# Rev1.net
KiCad netlist of a schematic drawn in EAGLE
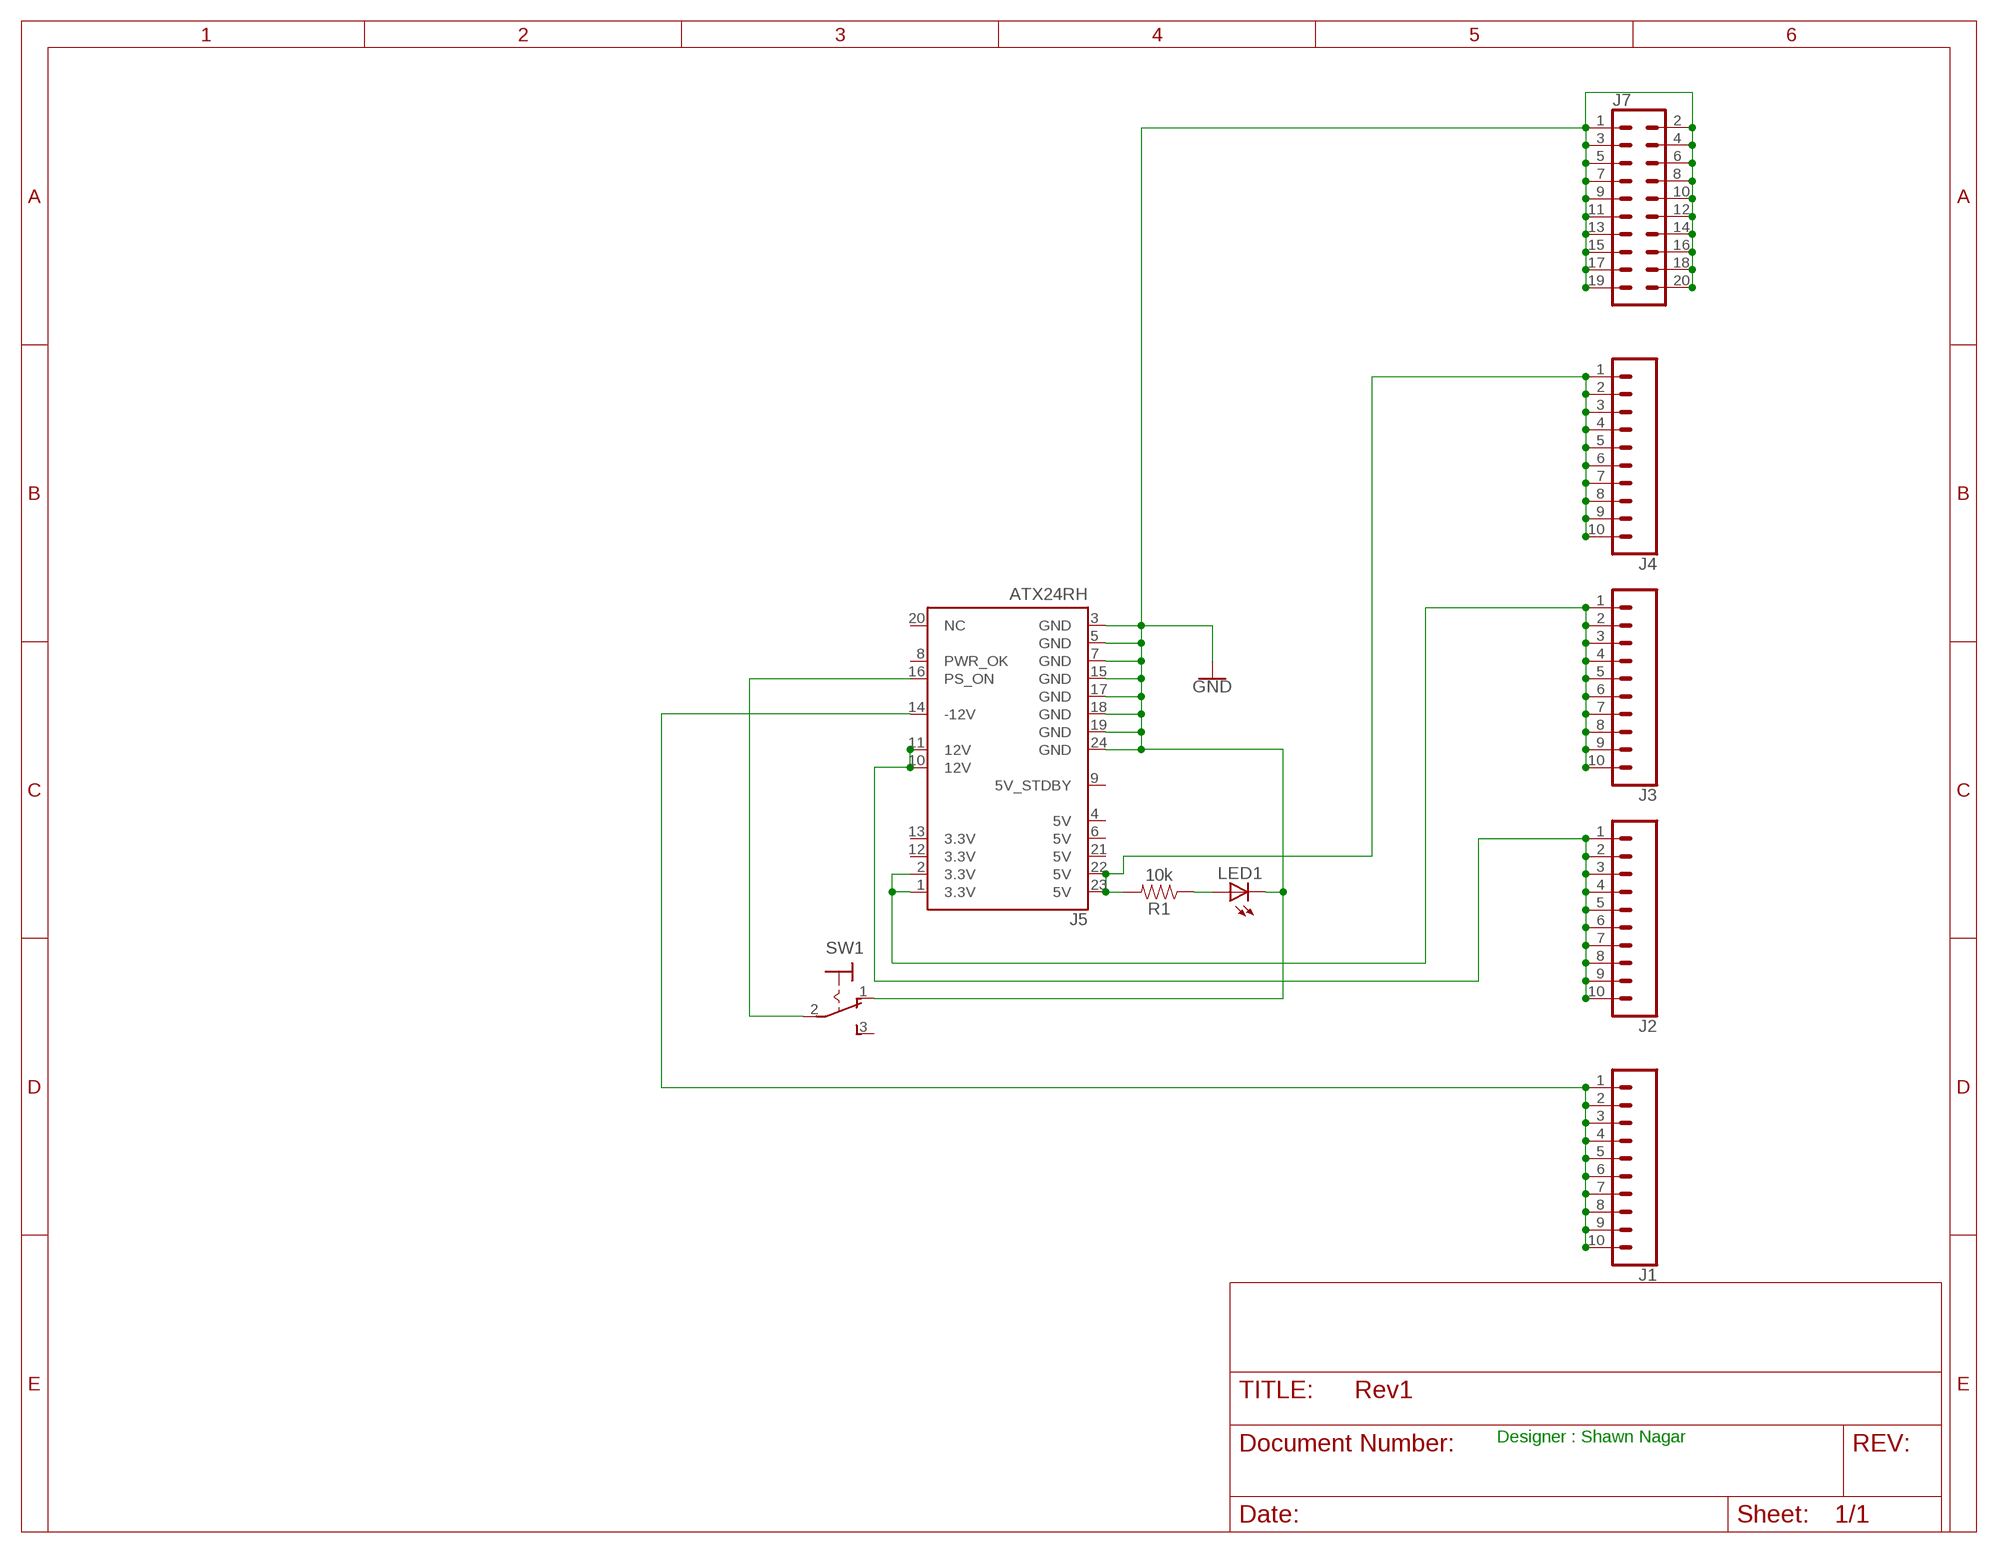
[diagram p0: schematic, sheet 1]

(export (version "E")
  (design (tool "Eeschema 10.0.6"))
  (components
    (comp (ref "J1")
      (value "CONN_10\"")
      (footprint "eagle-import:1X10")
      (libsource (lib "eagle-import") (part "CONN_10{dblquote}"))
    )
    (comp (ref "J2")
      (value "CONN_10\"")
      (footprint "eagle-import:1X10")
      (libsource (lib "eagle-import") (part "CONN_10{dblquote}"))
    )
    (comp (ref "J3")
      (value "CONN_10\"")
      (footprint "eagle-import:1X10")
      (libsource (lib "eagle-import") (part "CONN_10{dblquote}"))
    )
    (comp (ref "J4")
      (value "CONN_10\"")
      (footprint "eagle-import:1X10")
      (libsource (lib "eagle-import") (part "CONN_10{dblquote}"))
    )
    (comp (ref "J5")
      (value "ATX24RH")
      (footprint "eagle-import:ATX24_RIGHT_ANGLE")
      (libsource (lib "eagle-import") (part "ATX24RH"))
    )
    (comp (ref "J7")
      (value "CONN_10X2")
      (footprint "eagle-import:2X10")
      (libsource (lib "eagle-import") (part "CONN_10X2"))
    )
    (comp (ref "LED1")
      (value "LED5MM")
      (footprint "eagle-import:LED5MM")
      (libsource (lib "eagle-import") (part "LED5MM"))
    )
    (comp (ref "R1")
      (value "10k")
      (footprint "eagle-import:AXIAL-0.3")
      (libsource (lib "eagle-import") (part "10KOHM-HORIZ-1/4W-1%"))
    )
    (comp (ref "SW1")
      (value "320-916")
      (footprint "eagle-import:320-916")
      (libsource (lib "eagle-import") (part "320-916"))
    )
  )
  (nets
    (net (code "1") (name "GND") (class "Default")
      (node (ref "J5") (pin "15") (pinfunction "GND_15") (pintype "bidirectional"))
      (node (ref "J5") (pin "17") (pinfunction "GND_17") (pintype "bidirectional"))
      (node (ref "J5") (pin "18") (pinfunction "GND_18") (pintype "bidirectional"))
      (node (ref "J5") (pin "19") (pinfunction "GND_19") (pintype "bidirectional"))
      (node (ref "J5") (pin "24") (pinfunction "GND_24") (pintype "bidirectional"))
      (node (ref "J5") (pin "3") (pinfunction "GND_3") (pintype "bidirectional"))
      (node (ref "J5") (pin "5") (pinfunction "GND_5") (pintype "bidirectional"))
      (node (ref "J5") (pin "7") (pinfunction "GND_7") (pintype "bidirectional"))
      (node (ref "J7") (pin "1") (pinfunction "1_1") (pintype "passive"))
      (node (ref "J7") (pin "10") (pinfunction "10_10") (pintype "passive"))
      (node (ref "J7") (pin "11") (pinfunction "11_11") (pintype "passive"))
      (node (ref "J7") (pin "12") (pinfunction "12_12") (pintype "passive"))
      (node (ref "J7") (pin "13") (pinfunction "13_13") (pintype "passive"))
      (node (ref "J7") (pin "14") (pinfunction "14_14") (pintype "passive"))
      (node (ref "J7") (pin "15") (pinfunction "15_15") (pintype "passive"))
      (node (ref "J7") (pin "16") (pinfunction "16_16") (pintype "passive"))
      (node (ref "J7") (pin "17") (pinfunction "17_17") (pintype "passive"))
      (node (ref "J7") (pin "18") (pinfunction "18_18") (pintype "passive"))
      (node (ref "J7") (pin "19") (pinfunction "19_19") (pintype "passive"))
      (node (ref "J7") (pin "2") (pinfunction "2_2") (pintype "passive"))
      (node (ref "J7") (pin "20") (pinfunction "20_20") (pintype "passive"))
      (node (ref "J7") (pin "3") (pinfunction "3_3") (pintype "passive"))
      (node (ref "J7") (pin "4") (pinfunction "4_4") (pintype "passive"))
      (node (ref "J7") (pin "5") (pinfunction "5_5") (pintype "passive"))
      (node (ref "J7") (pin "6") (pinfunction "6_6") (pintype "passive"))
      (node (ref "J7") (pin "7") (pinfunction "7_7") (pintype "passive"))
      (node (ref "J7") (pin "8") (pinfunction "8_8") (pintype "passive"))
      (node (ref "J7") (pin "9") (pinfunction "9_9") (pintype "passive"))
      (node (ref "LED1") (pin "K") (pinfunction "C_K") (pintype "passive"))
      (node (ref "SW1") (pin "1") (pinfunction "O_1") (pintype "passive"))
    )
    (net (code "2") (name "Net-(J2-Pad1)") (class "Default")
      (node (ref "J2") (pin "1") (pinfunction "1_1") (pintype "passive"))
      (node (ref "J2") (pin "10") (pinfunction "10_10") (pintype "passive"))
      (node (ref "J2") (pin "2") (pinfunction "2_2") (pintype "passive"))
      (node (ref "J2") (pin "3") (pinfunction "3_3") (pintype "passive"))
      (node (ref "J2") (pin "4") (pinfunction "4_4") (pintype "passive"))
      (node (ref "J2") (pin "5") (pinfunction "5_5") (pintype "passive"))
      (node (ref "J2") (pin "6") (pinfunction "6_6") (pintype "passive"))
      (node (ref "J2") (pin "7") (pinfunction "7_7") (pintype "passive"))
      (node (ref "J2") (pin "8") (pinfunction "8_8") (pintype "passive"))
      (node (ref "J2") (pin "9") (pinfunction "9_9") (pintype "passive"))
      (node (ref "J5") (pin "10") (pinfunction "12V_10") (pintype "bidirectional"))
      (node (ref "J5") (pin "11") (pinfunction "12V_11") (pintype "bidirectional"))
    )
    (net (code "3") (name "Net-(J3-Pad1)") (class "Default")
      (node (ref "J3") (pin "1") (pinfunction "1_1") (pintype "passive"))
      (node (ref "J3") (pin "10") (pinfunction "10_10") (pintype "passive"))
      (node (ref "J3") (pin "2") (pinfunction "2_2") (pintype "passive"))
      (node (ref "J3") (pin "3") (pinfunction "3_3") (pintype "passive"))
      (node (ref "J3") (pin "4") (pinfunction "4_4") (pintype "passive"))
      (node (ref "J3") (pin "5") (pinfunction "5_5") (pintype "passive"))
      (node (ref "J3") (pin "6") (pinfunction "6_6") (pintype "passive"))
      (node (ref "J3") (pin "7") (pinfunction "7_7") (pintype "passive"))
      (node (ref "J3") (pin "8") (pinfunction "8_8") (pintype "passive"))
      (node (ref "J3") (pin "9") (pinfunction "9_9") (pintype "passive"))
      (node (ref "J5") (pin "1") (pinfunction "3.3V_1") (pintype "bidirectional"))
      (node (ref "J5") (pin "2") (pinfunction "3.3V_2") (pintype "bidirectional"))
    )
    (net (code "4") (name "Net-(J5--12V)") (class "Default")
      (node (ref "J1") (pin "1") (pinfunction "1_1") (pintype "passive"))
      (node (ref "J1") (pin "10") (pinfunction "10_10") (pintype "passive"))
      (node (ref "J1") (pin "2") (pinfunction "2_2") (pintype "passive"))
      (node (ref "J1") (pin "3") (pinfunction "3_3") (pintype "passive"))
      (node (ref "J1") (pin "4") (pinfunction "4_4") (pintype "passive"))
      (node (ref "J1") (pin "5") (pinfunction "5_5") (pintype "passive"))
      (node (ref "J1") (pin "6") (pinfunction "6_6") (pintype "passive"))
      (node (ref "J1") (pin "7") (pinfunction "7_7") (pintype "passive"))
      (node (ref "J1") (pin "8") (pinfunction "8_8") (pintype "passive"))
      (node (ref "J1") (pin "9") (pinfunction "9_9") (pintype "passive"))
      (node (ref "J5") (pin "14") (pinfunction "-12V_14") (pintype "bidirectional"))
    )
    (net (code "5") (name "Net-(J5-PS_ON)") (class "Default")
      (node (ref "J5") (pin "16") (pinfunction "PS_ON_16") (pintype "bidirectional"))
      (node (ref "SW1") (pin "2") (pinfunction "P_2") (pintype "passive"))
    )
    (net (code "6") (name "Net-(R1-1)") (class "Default")
      (node (ref "LED1") (pin "A") (pinfunction "A_A") (pintype "passive"))
      (node (ref "R1") (pin "P$1") (pinfunction "1_P$1") (pintype "passive"))
    )
    (net (code "7") (name "Net-(R1-2)") (class "Default")
      (node (ref "J4") (pin "1") (pinfunction "1_1") (pintype "passive"))
      (node (ref "J4") (pin "10") (pinfunction "10_10") (pintype "passive"))
      (node (ref "J4") (pin "2") (pinfunction "2_2") (pintype "passive"))
      (node (ref "J4") (pin "3") (pinfunction "3_3") (pintype "passive"))
      (node (ref "J4") (pin "4") (pinfunction "4_4") (pintype "passive"))
      (node (ref "J4") (pin "5") (pinfunction "5_5") (pintype "passive"))
      (node (ref "J4") (pin "6") (pinfunction "6_6") (pintype "passive"))
      (node (ref "J4") (pin "7") (pinfunction "7_7") (pintype "passive"))
      (node (ref "J4") (pin "8") (pinfunction "8_8") (pintype "passive"))
      (node (ref "J4") (pin "9") (pinfunction "9_9") (pintype "passive"))
      (node (ref "J5") (pin "22") (pinfunction "5V_22") (pintype "bidirectional"))
      (node (ref "J5") (pin "23") (pinfunction "5V_23") (pintype "bidirectional"))
      (node (ref "R1") (pin "P$2") (pinfunction "2_P$2") (pintype "passive"))
    )
    (net (code "8") (name "unconnected-(J5-3.3V-Pad12)") (class "Default")
      (node (ref "J5") (pin "12") (pinfunction "3.3V_12") (pintype "bidirectional"))
    )
    (net (code "9") (name "unconnected-(J5-3.3V-Pad13)") (class "Default")
      (node (ref "J5") (pin "13") (pinfunction "3.3V_13") (pintype "bidirectional"))
    )
    (net (code "10") (name "unconnected-(J5-5V-Pad4)") (class "Default")
      (node (ref "J5") (pin "4") (pinfunction "5V_4") (pintype "bidirectional"))
    )
    (net (code "11") (name "unconnected-(J5-5V-Pad6)") (class "Default")
      (node (ref "J5") (pin "6") (pinfunction "5V_6") (pintype "bidirectional"))
    )
    (net (code "12") (name "unconnected-(J5-5V-Pad21)") (class "Default")
      (node (ref "J5") (pin "21") (pinfunction "5V_21") (pintype "bidirectional"))
    )
    (net (code "13") (name "unconnected-(J5-5V_STDBY-Pad9)") (class "Default")
      (node (ref "J5") (pin "9") (pinfunction "5V_STDBY_9") (pintype "bidirectional"))
    )
    (net (code "14") (name "unconnected-(J5-NC-Pad20)") (class "Default")
      (node (ref "J5") (pin "20") (pinfunction "NC_20") (pintype "bidirectional"))
    )
    (net (code "15") (name "unconnected-(J5-PWR_OK-Pad8)") (class "Default")
      (node (ref "J5") (pin "8") (pinfunction "PWR_OK_8") (pintype "bidirectional"))
    )
    (net (code "16") (name "unconnected-(SW1-S-Pad3)") (class "Default")
      (node (ref "SW1") (pin "3") (pinfunction "S_3") (pintype "passive"))
    )
  )
)
